# 117_03_TIMER_GATE.net
KiCad netlist of a schematic drawn in EAGLE
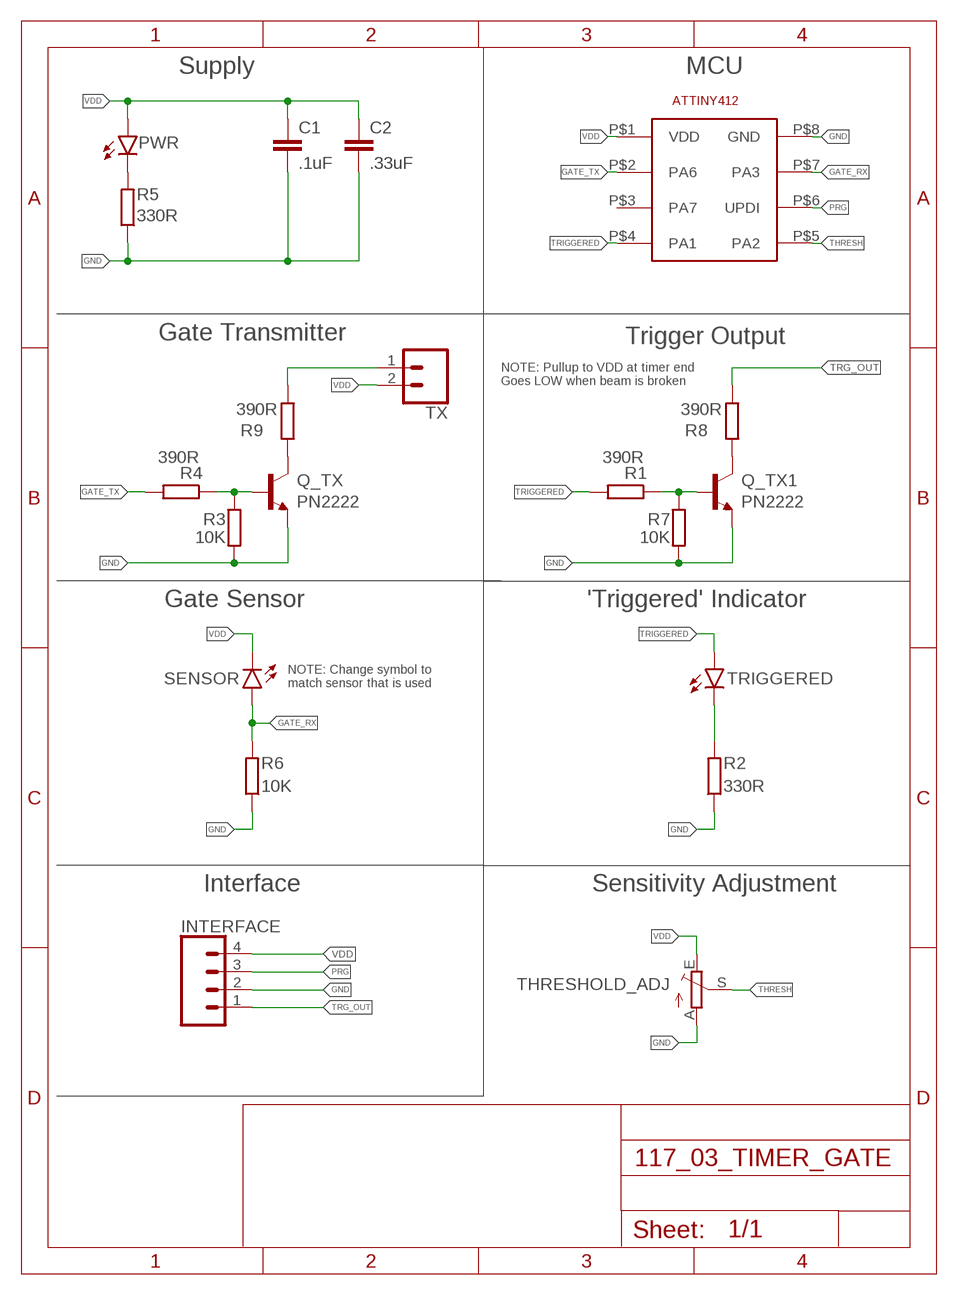
[diagram p0: schematic, sheet 1]

(export (version "E")
  (design (tool "Eeschema 10.0.6"))
  (components
    (comp (ref "C1")
      (value ".1uF")
      (footprint "eagle-import:C0805K")
      (libsource (lib "eagle-import") (part "C-EUC0805K"))
    )
    (comp (ref "C2")
      (value ".33uF")
      (footprint "eagle-import:C0805K")
      (libsource (lib "eagle-import") (part "C-EUC0805K"))
    )
    (comp (ref "INTERFACE")
      (value "CONN_04LONGPADS")
      (footprint "eagle-import:1X04_LONGPADS")
      (libsource (lib "eagle-import") (part "CONN_04LONGPADS"))
    )
    (comp (ref "PWR")
      (value "LEDSML0805")
      (footprint "eagle-import:SML0805")
      (libsource (lib "eagle-import") (part "LEDSML0805"))
    )
    (comp (ref "Q_TX")
      (value "PN2222")
      (footprint "eagle-import:TO92-EBC")
      (libsource (lib "eagle-import") (part "-NPN-TO92-EBC2N2222"))
    )
    (comp (ref "Q_TX1")
      (value "PN2222")
      (footprint "eagle-import:TO92-EBC")
      (libsource (lib "eagle-import") (part "-NPN-TO92-EBC2N2222"))
    )
    (comp (ref "R1")
      (value "390R")
      (footprint "eagle-import:M0805")
      (libsource (lib "eagle-import") (part "R-EU_M0805"))
    )
    (comp (ref "R2")
      (value "330R")
      (footprint "eagle-import:M0805")
      (libsource (lib "eagle-import") (part "R-EU_M0805"))
    )
    (comp (ref "R3")
      (value "10K")
      (footprint "eagle-import:M0805")
      (libsource (lib "eagle-import") (part "R-EU_M0805"))
    )
    (comp (ref "R4")
      (value "390R")
      (footprint "eagle-import:M0805")
      (libsource (lib "eagle-import") (part "R-EU_M0805"))
    )
    (comp (ref "R5")
      (value "330R")
      (footprint "eagle-import:M0805")
      (libsource (lib "eagle-import") (part "R-EU_M0805"))
    )
    (comp (ref "R6")
      (value "10K")
      (footprint "eagle-import:M0805")
      (libsource (lib "eagle-import") (part "R-EU_M0805"))
    )
    (comp (ref "R7")
      (value "10K")
      (footprint "eagle-import:M0805")
      (libsource (lib "eagle-import") (part "R-EU_M0805"))
    )
    (comp (ref "R8")
      (value "390R")
      (footprint "eagle-import:M0805")
      (libsource (lib "eagle-import") (part "R-EU_M0805"))
    )
    (comp (ref "R9")
      (value "390R")
      (footprint "eagle-import:M0805")
      (libsource (lib "eagle-import") (part "R-EU_M0805"))
    )
    (comp (ref "SENSOR")
      (value "LED5MM")
      (footprint "eagle-import:LED_5MM")
      (libsource (lib "eagle-import") (part "LED5MM"))
    )
    (comp (ref "THRESHOLD_ADJ")
      (value "TRIM_EU-S64W")
      (footprint "eagle-import:S64W")
      (libsource (lib "eagle-import") (part "TRIM_EU-S64W"))
    )
    (comp (ref "TRIGGERED")
      (value "LED5MM")
      (footprint "eagle-import:LED_5MM")
      (libsource (lib "eagle-import") (part "LED5MM"))
    )
    (comp (ref "TX")
      (value "CONN_02PTH3")
      (footprint "eagle-import:1X02_LONGPADS")
      (libsource (lib "eagle-import") (part "CONN_02PTH3"))
    )
    (comp (ref "U$1")
      (value "ATTINY412")
      (footprint "eagle-import:ATTINY412")
      (libsource (lib "eagle-import") (part "ATTINY412"))
    )
  )
  (nets
    (net (code "1") (name "GATE_RX") (class "Default")
      (node (ref "R6") (pin "2") (pinfunction "2_2") (pintype "passive"))
      (node (ref "SENSOR") (pin "A") (pinfunction "A_A") (pintype "passive"))
      (node (ref "U$1") (pin "P$7") (pinfunction "PA3_P$7") (pintype "bidirectional"))
    )
    (net (code "2") (name "GATE_TX") (class "Default")
      (node (ref "R4") (pin "2") (pinfunction "2_2") (pintype "passive"))
      (node (ref "U$1") (pin "P$2") (pinfunction "PA6_P$2") (pintype "bidirectional"))
    )
    (net (code "3") (name "GND") (class "Default")
      (node (ref "C1") (pin "2") (pinfunction "2_2") (pintype "passive"))
      (node (ref "C2") (pin "2") (pinfunction "2_2") (pintype "passive"))
      (node (ref "INTERFACE") (pin "2") (pinfunction "2_2") (pintype "passive"))
      (node (ref "Q_TX") (pin "E") (pinfunction "E_E") (pintype "passive"))
      (node (ref "Q_TX1") (pin "E") (pinfunction "E_E") (pintype "passive"))
      (node (ref "R2") (pin "1") (pinfunction "1_1") (pintype "passive"))
      (node (ref "R3") (pin "2") (pinfunction "2_2") (pintype "passive"))
      (node (ref "R5") (pin "1") (pinfunction "1_1") (pintype "passive"))
      (node (ref "R6") (pin "1") (pinfunction "1_1") (pintype "passive"))
      (node (ref "R7") (pin "2") (pinfunction "2_2") (pintype "passive"))
      (node (ref "THRESHOLD_ADJ") (pin "A") (pinfunction "A_A") (pintype "passive"))
      (node (ref "U$1") (pin "P$8") (pinfunction "GND_P$8") (pintype "bidirectional"))
    )
    (net (code "4") (name "Net-(PWR-PadC)") (class "Default")
      (node (ref "PWR") (pin "C") (pinfunction "C_C") (pintype "passive"))
      (node (ref "R5") (pin "2") (pinfunction "2_2") (pintype "passive"))
    )
    (net (code "5") (name "Net-(Q_TX-PadB)") (class "Default")
      (node (ref "Q_TX") (pin "B") (pinfunction "B_B") (pintype "passive"))
      (node (ref "R3") (pin "1") (pinfunction "1_1") (pintype "passive"))
      (node (ref "R4") (pin "1") (pinfunction "1_1") (pintype "passive"))
    )
    (net (code "6") (name "Net-(Q_TX-PadC)") (class "Default")
      (node (ref "Q_TX") (pin "C") (pinfunction "C_C") (pintype "passive"))
      (node (ref "R9") (pin "2") (pinfunction "2_2") (pintype "passive"))
    )
    (net (code "7") (name "Net-(Q_TX1-PadB)") (class "Default")
      (node (ref "Q_TX1") (pin "B") (pinfunction "B_B") (pintype "passive"))
      (node (ref "R1") (pin "1") (pinfunction "1_1") (pintype "passive"))
      (node (ref "R7") (pin "1") (pinfunction "1_1") (pintype "passive"))
    )
    (net (code "8") (name "Net-(Q_TX1-PadC)") (class "Default")
      (node (ref "Q_TX1") (pin "C") (pinfunction "C_C") (pintype "passive"))
      (node (ref "R8") (pin "2") (pinfunction "2_2") (pintype "passive"))
    )
    (net (code "9") (name "Net-(R9-Pad1)") (class "Default")
      (node (ref "R9") (pin "1") (pinfunction "1_1") (pintype "passive"))
      (node (ref "TX") (pin "1") (pinfunction "1_1") (pintype "passive"))
    )
    (net (code "10") (name "Net-(TRIGGERED-C)") (class "Default")
      (node (ref "R2") (pin "2") (pinfunction "2_2") (pintype "passive"))
      (node (ref "TRIGGERED") (pin "K") (pinfunction "C_K") (pintype "passive"))
    )
    (net (code "11") (name "PRG") (class "Default")
      (node (ref "INTERFACE") (pin "3") (pinfunction "3_3") (pintype "passive"))
      (node (ref "U$1") (pin "P$6") (pinfunction "UPDI_P$6") (pintype "bidirectional"))
    )
    (net (code "12") (name "THRESH") (class "Default")
      (node (ref "THRESHOLD_ADJ") (pin "S") (pinfunction "S_S") (pintype "passive"))
      (node (ref "U$1") (pin "P$5") (pinfunction "PA2_P$5") (pintype "bidirectional"))
    )
    (net (code "13") (name "TRG_OUT") (class "Default")
      (node (ref "INTERFACE") (pin "1") (pinfunction "1_1") (pintype "passive"))
      (node (ref "R8") (pin "1") (pinfunction "1_1") (pintype "passive"))
    )
    (net (code "14") (name "TRIGGERED") (class "Default")
      (node (ref "R1") (pin "2") (pinfunction "2_2") (pintype "passive"))
      (node (ref "TRIGGERED") (pin "A") (pinfunction "A_A") (pintype "passive"))
      (node (ref "U$1") (pin "P$4") (pinfunction "PA1_P$4") (pintype "bidirectional"))
    )
    (net (code "15") (name "VDD") (class "Default")
      (node (ref "C1") (pin "1") (pinfunction "1_1") (pintype "passive"))
      (node (ref "C2") (pin "1") (pinfunction "1_1") (pintype "passive"))
      (node (ref "INTERFACE") (pin "4") (pinfunction "4_4") (pintype "passive"))
      (node (ref "PWR") (pin "A") (pinfunction "A_A") (pintype "passive"))
      (node (ref "SENSOR") (pin "K") (pinfunction "C_K") (pintype "passive"))
      (node (ref "THRESHOLD_ADJ") (pin "E") (pinfunction "E_E") (pintype "passive"))
      (node (ref "TX") (pin "2") (pinfunction "2_2") (pintype "passive"))
      (node (ref "U$1") (pin "P$1") (pinfunction "VDD_P$1") (pintype "bidirectional"))
    )
    (net (code "16") (name "unconnected-(U$1-PA7-PadP$3)") (class "Default")
      (node (ref "U$1") (pin "P$3") (pinfunction "PA7_P$3") (pintype "bidirectional"))
    )
  )
)
